# STM32.net
KiCad netlist of a schematic drawn in Altium Designer
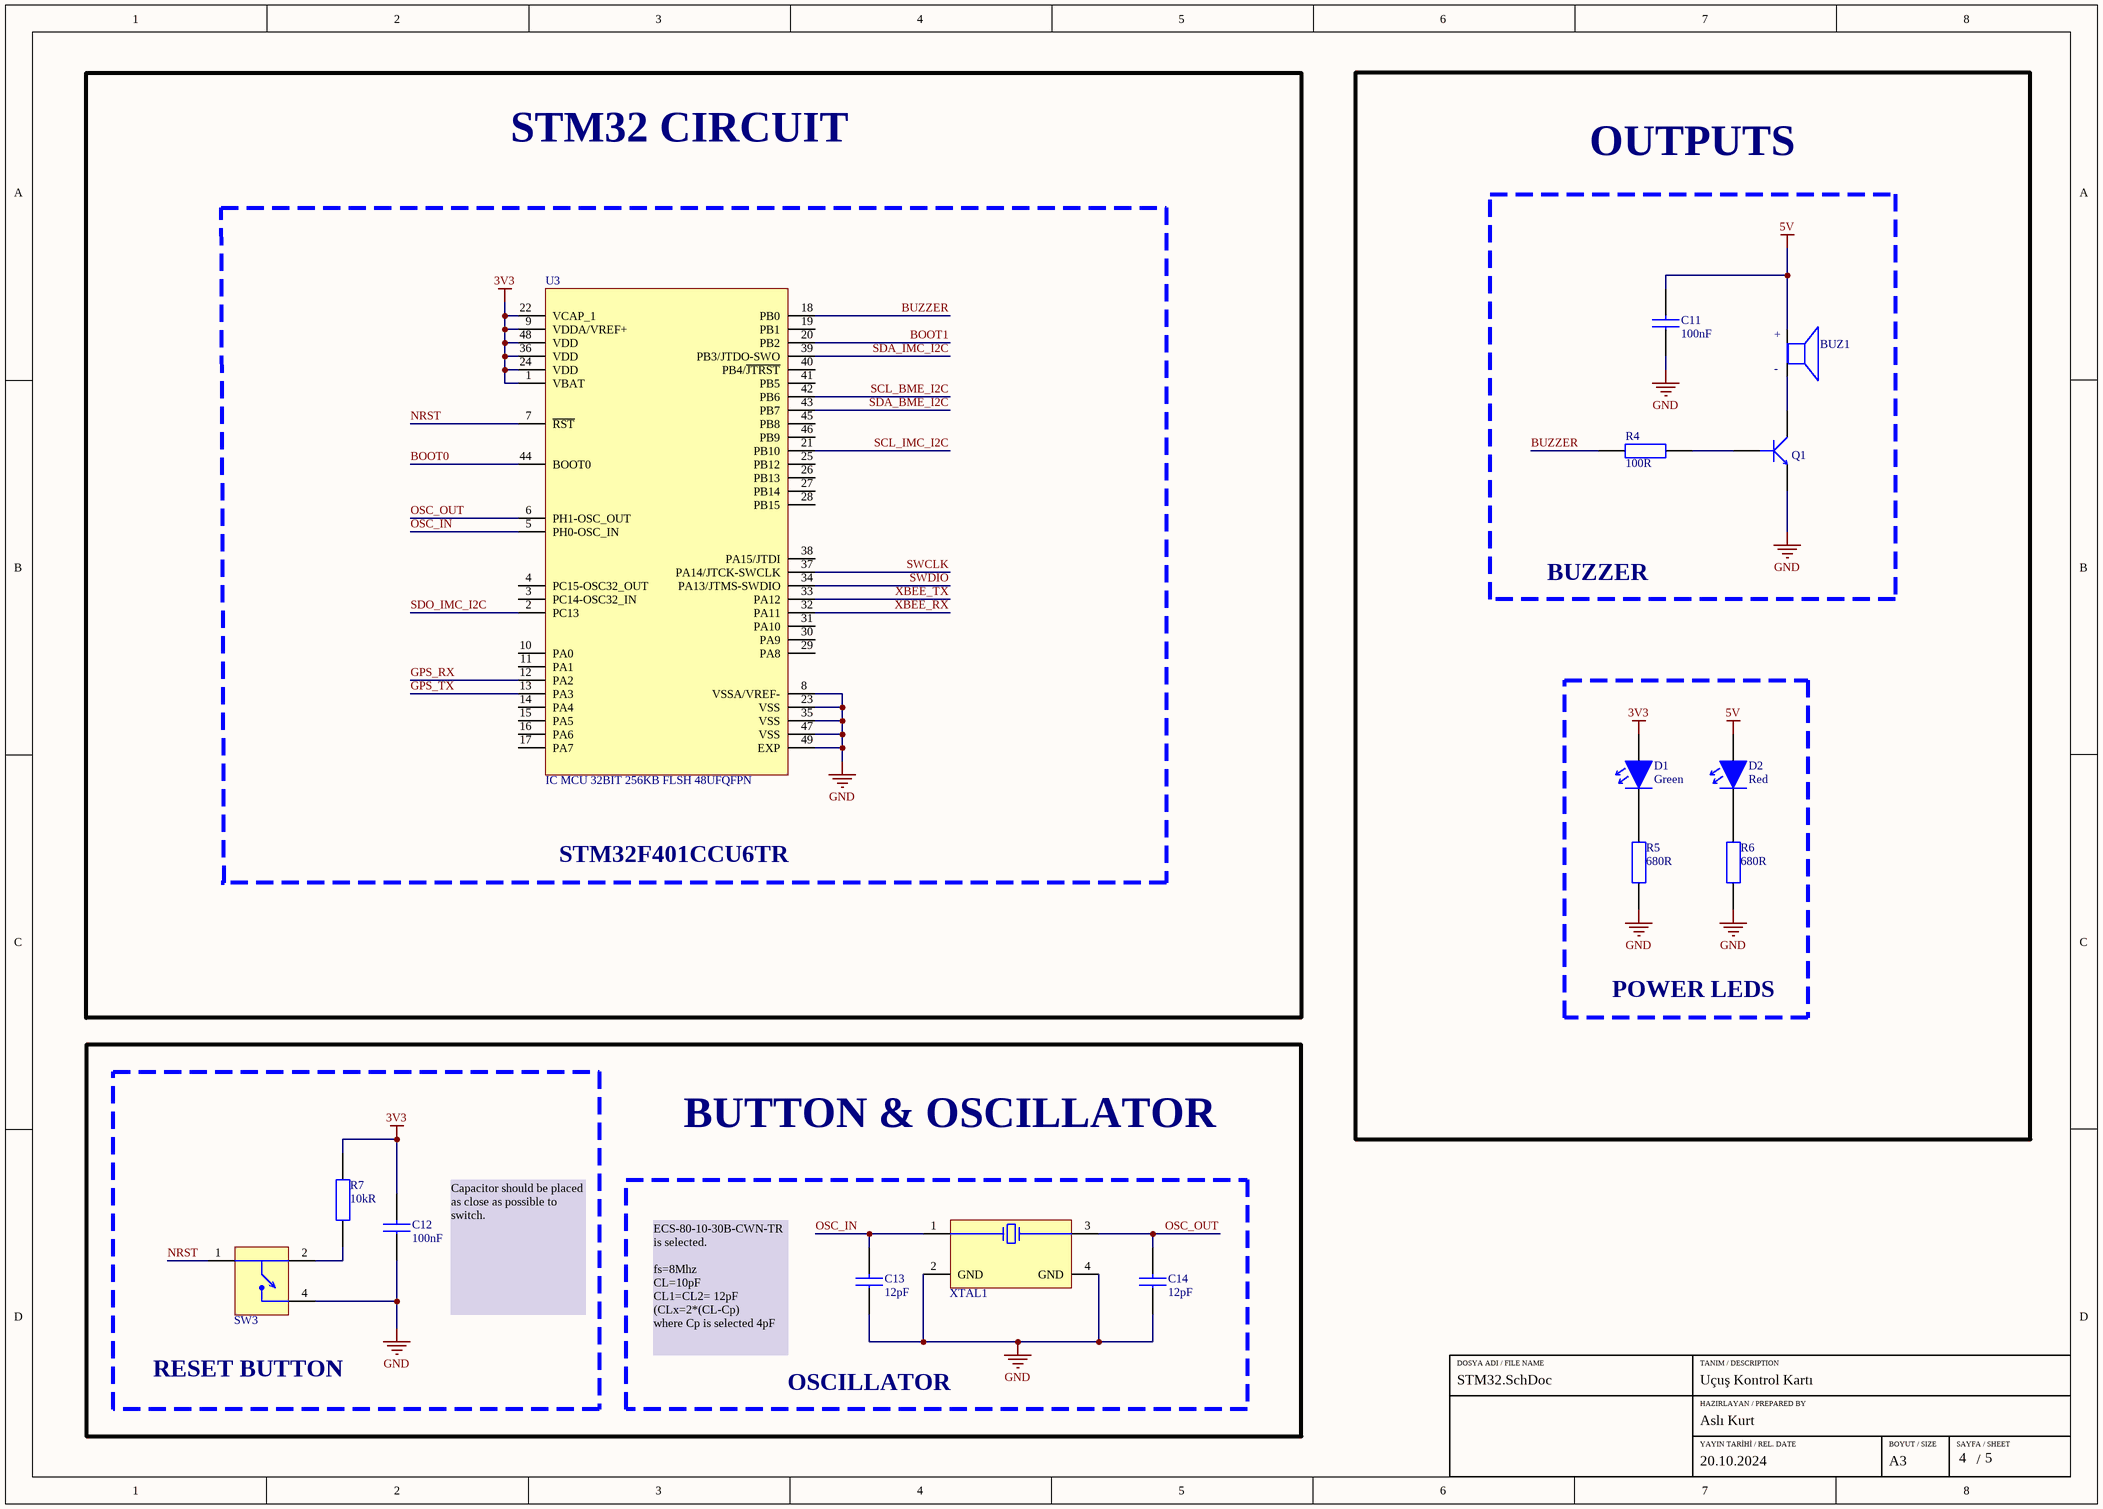
[diagram p0: STM32.SchDoc]

(export (version "E")
  (design (tool "Eeschema 10.0.6"))
  (components
    (comp (ref "BUZ1")
      (value "SMI-1027-TW-5V-R")
      (footprint "BUZZER_SMD")
      (description "Audio Indicator 5V 30mA 80dBA 2.7KHz Resonant Frequency SMD")
      (fields (field (name "MANUFACTURER") "Projects Unlimited") (field (name "DESIGNEDBY") "Aslı Kurt"))
      (libsource (lib "MyLibrary") (part "BUZZER_5V_SMD"))
    )
    (comp (ref "C11")
      (value "C0603C104K5RACTU")
      (footprint "CAP_0603")
      (description "CAP CER 100nF %10 0603 SMD")
      (fields
        (field (name "MANUFACTURER") "KEMET")
        (field (name "TOLERANCE") "10%")
        (field (name "CAPACITANCE") "100nF")
        (field (name "DESIGNEDBY") "Aslı Kurt")
      )
      (libsource (lib "MyLibrary") (part "CAP CER 100nF 0603"))
    )
    (comp (ref "C12")
      (value "C0603C104K5RACTU")
      (footprint "CAP_0603")
      (description "CAP CER 100nF %10 0603 SMD")
      (fields
        (field (name "MANUFACTURER") "KEMET")
        (field (name "TOLERANCE") "10%")
        (field (name "CAPACITANCE") "100nF")
        (field (name "DESIGNEDBY") "Aslı Kurt")
      )
      (libsource (lib "MyLibrary") (part "CAP CER 100nF 0603"))
    )
    (comp (ref "C13")
      (value "CC0603FRNPO9BN120")
      (footprint "CAP_0603")
      (description "Multilayer Ceramic Capacitor, 12 pF, 50 V, ï¿½ 1%, C0G (NP0), 0603 [1608 Metric]")
      (fields
        (field (name "MANUFACTURER") "Yageo")
        (field (name "TOLERANCE") "1%")
        (field (name "CAPACITANCE") "12pF")
        (field (name "DESIGNEDBY") "Aslı Kurt")
      )
      (libsource (lib "MyLibrary") (part "CAP CER 12pF 0603"))
    )
    (comp (ref "C14")
      (value "CC0603FRNPO9BN120")
      (footprint "CAP_0603")
      (description "Multilayer Ceramic Capacitor, 12 pF, 50 V, ï¿½ 1%, C0G (NP0), 0603 [1608 Metric]")
      (fields
        (field (name "MANUFACTURER") "Yageo")
        (field (name "TOLERANCE") "1%")
        (field (name "CAPACITANCE") "12pF")
        (field (name "DESIGNEDBY") "Aslı Kurt")
      )
      (libsource (lib "MyLibrary") (part "CAP CER 12pF 0603"))
    )
    (comp (ref "D1")
      (value "150120GS75000")
      (footprint "LED_GREEN_1206")
      (description "WL-SMCW SMT Mono-Color Chip LED Waterclear")
      (fields
        (field (name "MANUFACTURER") "Wurth Electronics")
        (field (name "COLOR") "Green")
        (field (name "DESIGNEDBY") "Aslı Kurt")
      )
      (libsource (lib "MyLibrary") (part "LED GREEN 1206"))
    )
    (comp (ref "D2")
      (value "LH R974-LP-1")
      (footprint "LED_RED_0805")
      (description "LED Uni-Color Hyper Red 660nm 2-Pin Chip 0805(2012Metric) T/R")
      (fields
        (field (name "MANUFACTURER") "Osram Opto")
        (field (name "COLOR") "Red")
        (field (name "DESIGNEDBY") "Aslı Kurt")
      )
      (libsource (lib "MyLibrary") (part "LED RED 0805"))
    )
    (comp (ref "Q1")
      (value "MMBT3904-7-F")
      (footprint "SOT-23F")
      (description "Transistor General Purpose BJT NPN 40 Volt 0.2A Automotive 3-Pin SOT-23")
      (fields (field (name "MANUFACTURER") "Diodes Zetex") (field (name "DESIGNEDBY") "Aslı Kurt"))
      (libsource (lib "MyLibrary") (part "MMBT3904-7-F"))
    )
    (comp (ref "R4")
      (value "RC0603JR-07100RL")
      (footprint "RES_0603")
      (description "RES 100 %5 OHM 0603 SMD")
      (fields
        (field (name "MANUFACTURER") "Yageo")
        (field (name "TOLERANCE") "5%")
        (field (name "RESISTANCE") "100R")
        (field (name "DESIGNEDBY") "Aslı Kurt")
      )
      (libsource (lib "MyLibrary") (part "RES 100 OHM 0603"))
    )
    (comp (ref "R5")
      (value "RC1206FR-07680RL")
      (footprint "RES_1206")
      (description "SMD Chip Resistor, 680 Ohm, ï¿½ 1%, 250 mW, 1206 [3216 Metric], Thick Film, General Purpose")
      (fields
        (field (name "MANUFACTURER") "Yageo")
        (field (name "RESISTANCE") "680R")
        (field (name "DESIGNEDBY") "Aslı Kurt")
      )
      (libsource (lib "MyLibrary") (part "RES 680 OHM 1206"))
    )
    (comp (ref "R6")
      (value "RC1206FR-07680RL")
      (footprint "RES_1206")
      (description "SMD Chip Resistor, 680 Ohm, ï¿½ 1%, 250 mW, 1206 [3216 Metric], Thick Film, General Purpose")
      (fields
        (field (name "MANUFACTURER") "Yageo")
        (field (name "RESISTANCE") "680R")
        (field (name "DESIGNEDBY") "Aslı Kurt")
      )
      (libsource (lib "MyLibrary") (part "RES 680 OHM 1206"))
    )
    (comp (ref "R7")
      (value "RC0603FR-0710KL")
      (footprint "RES_0603")
      (description "RES 10K %1 OHM 0603 SMD")
      (fields
        (field (name "MANUFACTURER") "Yageo")
        (field (name "TOLERANCE") "1%")
        (field (name "RESISTANCE") "10kR")
        (field (name "DESIGNEDBY") "Aslı Kurt")
      )
      (libsource (lib "MyLibrary") (part "RES 10K OHM 0603"))
    )
    (comp (ref "SW3")
      (value "PTS815 SJK 250 SMTR LFS")
      (footprint "BUTTON SMD")
      (description "Microminiature Top Actuated Tactile Switch Momentary SPST-NO 50mA 12VDC Surface Mount T/R")
      (fields
        (field (name "MANUFACTURER") "ITT C&K")
        (field (name "MANUFACTURER PART NUMBER") "PTS815SJK250SMTRLFS")
        (field (name "DESIGNEDBY") "Aslı Kurt")
      )
      (libsource (lib "MyLibrary") (part "4.2mm x 3.2mm BUTTON"))
    )
    (comp (ref "U3")
      (value "IC MCU 32BIT 256KB FLSH 48UFQFPN")
      (footprint "48-UFQFPN (7x7)")
      (description "MCU 32-bit STM32 ARM Cortex M4 RISC 256KB Flash 1.8V/2.5V/3.3V 48-Pin UFQFPN EP Tray")
      (fields
        (field (name "MANUFACTURER") "STMicroelectronics")
        (field (name "MANUFACTURER PART NUMBER") "STM32F401CCU6")
        (field (name "DESIGNEDBY") "Aslı Kurt")
      )
      (libsource (lib "MyLibrary") (part "STM32F401CCU6"))
    )
    (comp (ref "XTAL1")
      (value "ECS-80-10-30B-CWN-TR")
      (footprint "4-SMD, No Lead")
      (description "Crystal 8MHz ±10ppm (Tol) ±15ppm (Stability) 10pF FUND 100Ohm 4-Pin Mini-SMD T/R")
      (fields (field (name "MANUFACTURER") "ECS International") (field (name "DESIGNEDBY") "Aslı Kurt"))
      (libsource (lib "MyLibrary") (part "ECS-80-10-30B-CWN-TR"))
    )
  )
  (nets
    (net (code "1") (name "/BOOT0") (class "Default")
      (node (ref "U3") (pin "44") (pinfunction "BOOT0_44") (pintype "passive"))
    )
    (net (code "2") (name "/BOOT1") (class "Default")
      (node (ref "U3") (pin "20") (pinfunction "PB2_20") (pintype "passive"))
    )
    (net (code "3") (name "/BUZZER") (class "Default")
      (node (ref "R4") (pin "1") (pinfunction "1_1") (pintype "passive"))
      (node (ref "U3") (pin "18") (pinfunction "PB0_18") (pintype "passive"))
    )
    (net (code "4") (name "/GPS_RX") (class "Default")
      (node (ref "U3") (pin "12") (pinfunction "PA2_12") (pintype "passive"))
    )
    (net (code "5") (name "/GPS_TX") (class "Default")
      (node (ref "U3") (pin "13") (pinfunction "PA3_13") (pintype "passive"))
    )
    (net (code "6") (name "/NRST") (class "Default")
      (node (ref "SW3") (pin "1") (pinfunction "1_1") (pintype "passive"))
      (node (ref "U3") (pin "7") (pinfunction "~{RST}_7") (pintype "passive"))
    )
    (net (code "7") (name "/OSC_IN") (class "Default")
      (node (ref "C13") (pin "2") (pinfunction "2_2") (pintype "passive"))
      (node (ref "U3") (pin "5") (pinfunction "PH0-OSC_IN_5") (pintype "passive"))
      (node (ref "XTAL1") (pin "1") (pinfunction "1_1") (pintype "passive"))
    )
    (net (code "8") (name "/OSC_OUT") (class "Default")
      (node (ref "C14") (pin "2") (pinfunction "2_2") (pintype "passive"))
      (node (ref "U3") (pin "6") (pinfunction "PH1-OSC_OUT_6") (pintype "passive"))
      (node (ref "XTAL1") (pin "3") (pinfunction "3_3") (pintype "passive"))
    )
    (net (code "9") (name "/SCL_BME_I2C") (class "Default")
      (node (ref "U3") (pin "42") (pinfunction "PB6_42") (pintype "passive"))
    )
    (net (code "10") (name "/SCL_IMC_I2C") (class "Default")
      (node (ref "U3") (pin "21") (pinfunction "PB10_21") (pintype "passive"))
    )
    (net (code "11") (name "/SDA_BME_I2C") (class "Default")
      (node (ref "U3") (pin "43") (pinfunction "PB7_43") (pintype "passive"))
    )
    (net (code "12") (name "/SDA_IMC_I2C") (class "Default")
      (node (ref "U3") (pin "39") (pinfunction "PB3/JTDO-SWO_39") (pintype "passive"))
    )
    (net (code "13") (name "/SDO_IMC_I2C") (class "Default")
      (node (ref "U3") (pin "2") (pinfunction "PC13_2") (pintype "passive"))
    )
    (net (code "14") (name "/SWCLK") (class "Default")
      (node (ref "U3") (pin "37") (pinfunction "PA14/JTCK-SWCLK_37") (pintype "passive"))
    )
    (net (code "15") (name "/SWDIO") (class "Default")
      (node (ref "U3") (pin "34") (pinfunction "PA13/JTMS-SWDIO_34") (pintype "passive"))
    )
    (net (code "16") (name "/XBEE_RX") (class "Default")
      (node (ref "U3") (pin "32") (pinfunction "PA11_32") (pintype "passive"))
    )
    (net (code "17") (name "/XBEE_TX") (class "Default")
      (node (ref "U3") (pin "33") (pinfunction "PA12_33") (pintype "passive"))
    )
    (net (code "18") (name "3V3") (class "Default")
      (node (ref "C12") (pin "2") (pinfunction "2_2") (pintype "passive"))
      (node (ref "D1") (pin "2") (pinfunction "2_2") (pintype "power_in"))
      (node (ref "R7") (pin "2") (pinfunction "2_2") (pintype "passive"))
      (node (ref "U3") (pin "1") (pinfunction "VBAT_1") (pintype "passive"))
      (node (ref "U3") (pin "22") (pinfunction "VCAP_1_22") (pintype "passive"))
      (node (ref "U3") (pin "24") (pinfunction "VDD_24") (pintype "passive"))
      (node (ref "U3") (pin "36") (pinfunction "VDD_36") (pintype "passive"))
      (node (ref "U3") (pin "48") (pinfunction "VDD_48") (pintype "passive"))
      (node (ref "U3") (pin "9") (pinfunction "VDDA/VREF+_9") (pintype "passive"))
    )
    (net (code "19") (name "5V") (class "Default")
      (node (ref "BUZ1") (pin "P") (pinfunction "POS_P") (pintype "passive"))
      (node (ref "C11") (pin "2") (pinfunction "2_2") (pintype "passive"))
      (node (ref "D2") (pin "2") (pinfunction "2_2") (pintype "power_in"))
    )
    (net (code "20") (name "GND") (class "Default")
      (node (ref "C11") (pin "1") (pinfunction "1_1") (pintype "passive"))
      (node (ref "C12") (pin "1") (pinfunction "1_1") (pintype "passive"))
      (node (ref "C13") (pin "1") (pinfunction "1_1") (pintype "passive"))
      (node (ref "C14") (pin "1") (pinfunction "1_1") (pintype "passive"))
      (node (ref "Q1") (pin "2") (pinfunction "E_2") (pintype "power_in"))
      (node (ref "R5") (pin "1") (pinfunction "1_1") (pintype "passive"))
      (node (ref "R6") (pin "1") (pinfunction "1_1") (pintype "passive"))
      (node (ref "SW3") (pin "4") (pinfunction "4_4") (pintype "passive"))
      (node (ref "U3") (pin "23") (pinfunction "VSS_23") (pintype "passive"))
      (node (ref "U3") (pin "35") (pinfunction "VSS_35") (pintype "passive"))
      (node (ref "U3") (pin "47") (pinfunction "VSS_47") (pintype "passive"))
      (node (ref "U3") (pin "49") (pinfunction "EXP_49") (pintype "passive"))
      (node (ref "U3") (pin "8") (pinfunction "VSSA/VREF-_8") (pintype "passive"))
      (node (ref "XTAL1") (pin "2") (pinfunction "GND_2") (pintype "passive"))
      (node (ref "XTAL1") (pin "4") (pinfunction "GND_4") (pintype "passive"))
    )
    (net (code "21") (name "Net-(BUZ1-NEG)") (class "Default")
      (node (ref "BUZ1") (pin "N") (pinfunction "NEG_N") (pintype "passive"))
      (node (ref "Q1") (pin "3") (pinfunction "C_3") (pintype "power_in"))
    )
    (net (code "22") (name "Net-(D1-Pad1)") (class "Default")
      (node (ref "D1") (pin "1") (pinfunction "1_1") (pintype "power_in"))
      (node (ref "R5") (pin "2") (pinfunction "2_2") (pintype "passive"))
    )
    (net (code "23") (name "Net-(D2-Pad1)") (class "Default")
      (node (ref "D2") (pin "1") (pinfunction "1_1") (pintype "power_in"))
      (node (ref "R6") (pin "2") (pinfunction "2_2") (pintype "passive"))
    )
    (net (code "24") (name "Net-(Q1-B)") (class "Default")
      (node (ref "Q1") (pin "1") (pinfunction "B_1") (pintype "power_in"))
      (node (ref "R4") (pin "2") (pinfunction "2_2") (pintype "passive"))
    )
    (net (code "25") (name "Net-(R7-Pad1)") (class "Default")
      (node (ref "R7") (pin "1") (pinfunction "1_1") (pintype "passive"))
      (node (ref "SW3") (pin "2") (pinfunction "2_2") (pintype "passive"))
    )
    (net (code "26") (name "unconnected-(U3-PA0-Pad10)") (class "Default")
      (node (ref "U3") (pin "10") (pinfunction "PA0_10") (pintype "passive"))
    )
    (net (code "27") (name "unconnected-(U3-PA1-Pad11)") (class "Default")
      (node (ref "U3") (pin "11") (pinfunction "PA1_11") (pintype "passive"))
    )
    (net (code "28") (name "unconnected-(U3-PA4-Pad14)") (class "Default")
      (node (ref "U3") (pin "14") (pinfunction "PA4_14") (pintype "passive"))
    )
    (net (code "29") (name "unconnected-(U3-PA5-Pad15)") (class "Default")
      (node (ref "U3") (pin "15") (pinfunction "PA5_15") (pintype "passive"))
    )
    (net (code "30") (name "unconnected-(U3-PA6-Pad16)") (class "Default")
      (node (ref "U3") (pin "16") (pinfunction "PA6_16") (pintype "passive"))
    )
    (net (code "31") (name "unconnected-(U3-PA7-Pad17)") (class "Default")
      (node (ref "U3") (pin "17") (pinfunction "PA7_17") (pintype "passive"))
    )
    (net (code "32") (name "unconnected-(U3-PA8-Pad29)") (class "Default")
      (node (ref "U3") (pin "29") (pinfunction "PA8_29") (pintype "passive"))
    )
    (net (code "33") (name "unconnected-(U3-PA9-Pad30)") (class "Default")
      (node (ref "U3") (pin "30") (pinfunction "PA9_30") (pintype "passive"))
    )
    (net (code "34") (name "unconnected-(U3-PA10-Pad31)") (class "Default")
      (node (ref "U3") (pin "31") (pinfunction "PA10_31") (pintype "passive"))
    )
    (net (code "35") (name "unconnected-(U3-PA15{slash}JTDI-Pad38)") (class "Default")
      (node (ref "U3") (pin "38") (pinfunction "PA15/JTDI_38") (pintype "passive"))
    )
    (net (code "36") (name "unconnected-(U3-PB1-Pad19)") (class "Default")
      (node (ref "U3") (pin "19") (pinfunction "PB1_19") (pintype "passive"))
    )
    (net (code "37") (name "unconnected-(U3-PB4{slash}~{JTRST}-Pad40)") (class "Default")
      (node (ref "U3") (pin "40") (pinfunction "PB4/~{JTRST}_40") (pintype "passive"))
    )
    (net (code "38") (name "unconnected-(U3-PB5-Pad41)") (class "Default")
      (node (ref "U3") (pin "41") (pinfunction "PB5_41") (pintype "passive"))
    )
    (net (code "39") (name "unconnected-(U3-PB8-Pad45)") (class "Default")
      (node (ref "U3") (pin "45") (pinfunction "PB8_45") (pintype "passive"))
    )
    (net (code "40") (name "unconnected-(U3-PB9-Pad46)") (class "Default")
      (node (ref "U3") (pin "46") (pinfunction "PB9_46") (pintype "passive"))
    )
    (net (code "41") (name "unconnected-(U3-PB12-Pad25)") (class "Default")
      (node (ref "U3") (pin "25") (pinfunction "PB12_25") (pintype "passive"))
    )
    (net (code "42") (name "unconnected-(U3-PB13-Pad26)") (class "Default")
      (node (ref "U3") (pin "26") (pinfunction "PB13_26") (pintype "passive"))
    )
    (net (code "43") (name "unconnected-(U3-PB14-Pad27)") (class "Default")
      (node (ref "U3") (pin "27") (pinfunction "PB14_27") (pintype "passive"))
    )
    (net (code "44") (name "unconnected-(U3-PB15-Pad28)") (class "Default")
      (node (ref "U3") (pin "28") (pinfunction "PB15_28") (pintype "passive"))
    )
    (net (code "45") (name "unconnected-(U3-PC14-OSC32_IN-Pad3)") (class "Default")
      (node (ref "U3") (pin "3") (pinfunction "PC14-OSC32_IN_3") (pintype "passive"))
    )
    (net (code "46") (name "unconnected-(U3-PC15-OSC32_OUT-Pad4)") (class "Default")
      (node (ref "U3") (pin "4") (pinfunction "PC15-OSC32_OUT_4") (pintype "passive"))
    )
  )
)
